# Mergen_Telemetri_Ate_leme.net
KiCad netlist of a schematic drawn in EAGLE
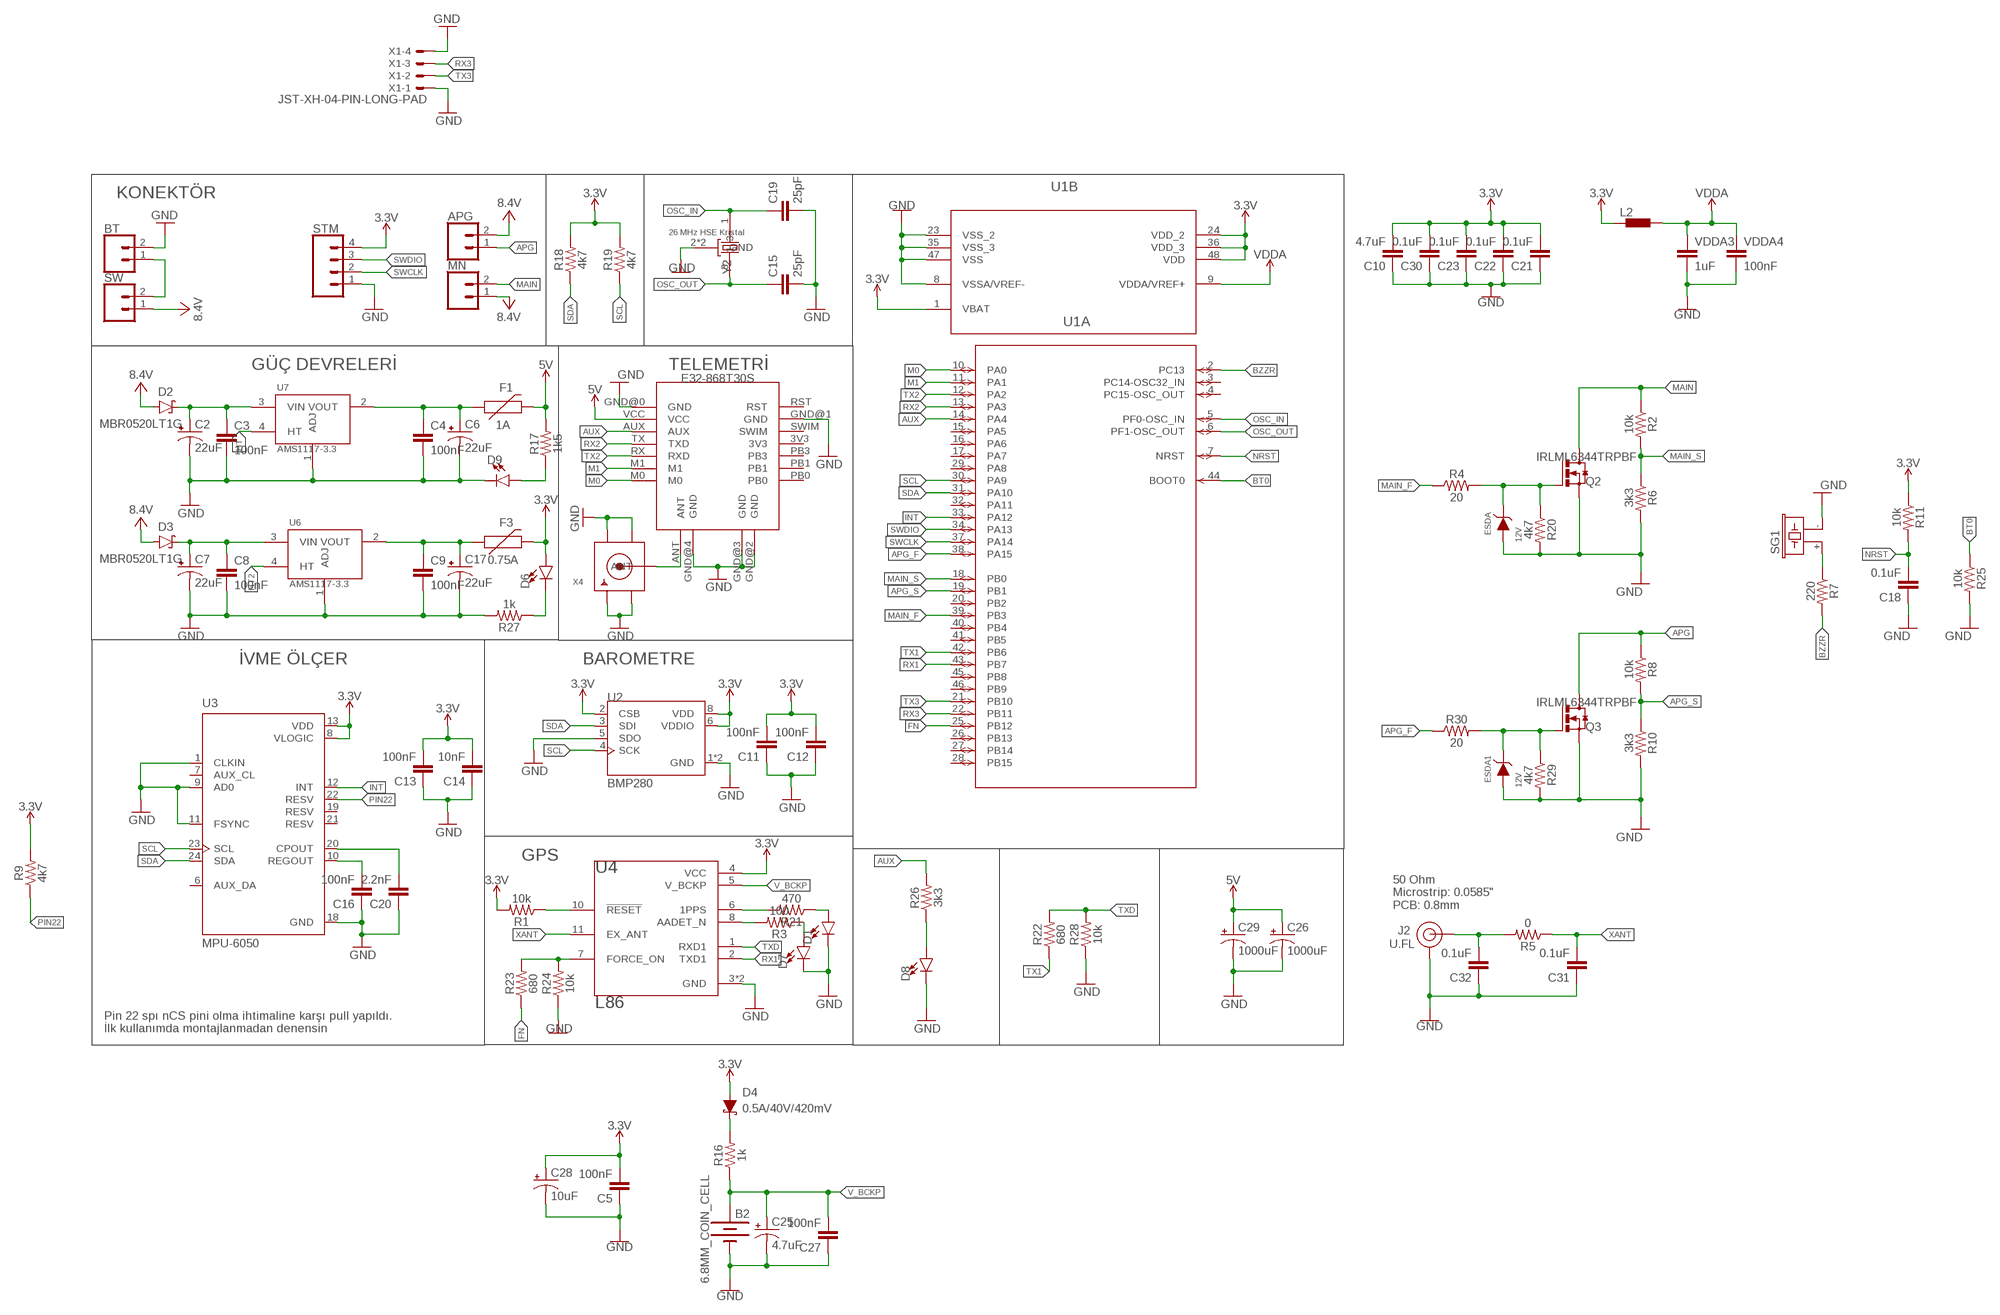
[diagram p0: schematic, sheet 1]

(export (version "E")
  (design (tool "Eeschema 10.0.6"))
  (components
    (comp (ref "APG")
      (value "CONN_02POLAR")
      (footprint "eagle-import:MOLEX-1X2")
      (libsource (lib "eagle-import") (part "CONN_02POLAR"))
    )
    (comp (ref "B2")
      (value "6.8MM_COIN_CELL")
      (footprint "eagle-import:BATTCON-6.8MM")
      (libsource (lib "eagle-import") (part "BATTERY-6.8MM_SMD"))
    )
    (comp (ref "BT")
      (value "CONN_02POLAR")
      (footprint "eagle-import:MOLEX-1X2")
      (libsource (lib "eagle-import") (part "CONN_02POLAR"))
    )
    (comp (ref "C2")
      (value "22uF")
      (footprint "eagle-import:EIA3528")
      (libsource (lib "eagle-import") (part "47UF-POLAR-EIA3528-10V-10%"))
    )
    (comp (ref "C3")
      (value "100nF")
      (footprint "eagle-import:0603")
      (libsource (lib "eagle-import") (part "1.0UF-0603-16V-10%"))
    )
    (comp (ref "C4")
      (value "100nF")
      (footprint "eagle-import:0603")
      (libsource (lib "eagle-import") (part "1.0UF-0603-16V-10%"))
    )
    (comp (ref "C5")
      (value "100nF")
      (footprint "eagle-import:0603")
      (libsource (lib "eagle-import") (part "1.0UF-0603-16V-10%"))
    )
    (comp (ref "C6")
      (value "22uF")
      (footprint "eagle-import:EIA3528")
      (libsource (lib "eagle-import") (part "47UF-POLAR-EIA3528-10V-10%"))
    )
    (comp (ref "C7")
      (value "22uF")
      (footprint "eagle-import:EIA3528")
      (libsource (lib "eagle-import") (part "47UF-POLAR-EIA3528-10V-10%"))
    )
    (comp (ref "C8")
      (value "100nF")
      (footprint "eagle-import:0603")
      (libsource (lib "eagle-import") (part "1.0UF-0603-16V-10%"))
    )
    (comp (ref "C9")
      (value "100nF")
      (footprint "eagle-import:0603")
      (libsource (lib "eagle-import") (part "1.0UF-0603-16V-10%"))
    )
    (comp (ref "C10")
      (value "4.7uF")
      (footprint "eagle-import:0603")
      (libsource (lib "eagle-import") (part "1.0UF-0603-16V-10%"))
    )
    (comp (ref "C11")
      (value "100nF")
      (footprint "eagle-import:0603")
      (libsource (lib "eagle-import") (part "1.0UF-0603-16V-10%"))
    )
    (comp (ref "C12")
      (value "100nF")
      (footprint "eagle-import:0603")
      (libsource (lib "eagle-import") (part "1.0UF-0603-16V-10%"))
    )
    (comp (ref "C13")
      (value "100nF")
      (footprint "eagle-import:0603")
      (libsource (lib "eagle-import") (part "1.0UF-0603-16V-10%"))
    )
    (comp (ref "C14")
      (value "10nF")
      (footprint "eagle-import:0603")
      (libsource (lib "eagle-import") (part "1.0UF-0603-16V-10%"))
    )
    (comp (ref "C15")
      (value "25pF")
      (footprint "eagle-import:0603")
      (libsource (lib "eagle-import") (part "1.0UF-0603-16V-10%"))
    )
    (comp (ref "C16")
      (value "100nF")
      (footprint "eagle-import:0603")
      (libsource (lib "eagle-import") (part "1.0UF-0603-16V-10%"))
    )
    (comp (ref "C17")
      (value "22uF")
      (footprint "eagle-import:EIA3528")
      (libsource (lib "eagle-import") (part "47UF-POLAR-EIA3528-10V-10%"))
    )
    (comp (ref "C18")
      (value "0.1uF")
      (footprint "eagle-import:0603")
      (libsource (lib "eagle-import") (part "1.0UF-0603-16V-10%"))
    )
    (comp (ref "C19")
      (value "25pF")
      (footprint "eagle-import:0603")
      (libsource (lib "eagle-import") (part "1.0UF-0603-16V-10%"))
    )
    (comp (ref "C20")
      (value "2.2nF")
      (footprint "eagle-import:0603")
      (libsource (lib "eagle-import") (part "1.0UF-0603-16V-10%"))
    )
    (comp (ref "C21")
      (value "0.1uF")
      (footprint "eagle-import:0603")
      (libsource (lib "eagle-import") (part "1.0UF-0603-16V-10%"))
    )
    (comp (ref "C22")
      (value "0.1uF")
      (footprint "eagle-import:0603")
      (libsource (lib "eagle-import") (part "1.0UF-0603-16V-10%"))
    )
    (comp (ref "C23")
      (value "0.1uF")
      (footprint "eagle-import:0603")
      (libsource (lib "eagle-import") (part "1.0UF-0603-16V-10%"))
    )
    (comp (ref "C25")
      (value "4.7uF")
      (footprint "eagle-import:EIA3528")
      (libsource (lib "eagle-import") (part "47UF-POLAR-EIA3528-10V-10%"))
    )
    (comp (ref "C26")
      (value "1000uF")
      (footprint "eagle-import:150CLZ-1010")
      (libsource (lib "eagle-import") (part "CPOL-US150CLZ-1010"))
    )
    (comp (ref "C27")
      (value "100nF")
      (footprint "eagle-import:0603")
      (libsource (lib "eagle-import") (part "1.0UF-0603-16V-10%"))
    )
    (comp (ref "C28")
      (value "10uF")
      (footprint "eagle-import:EIA3528")
      (libsource (lib "eagle-import") (part "47UF-POLAR-EIA3528-10V-10%"))
    )
    (comp (ref "C29")
      (value "1000uF")
      (footprint "eagle-import:150CLZ-1010")
      (libsource (lib "eagle-import") (part "CPOL-US150CLZ-1010"))
    )
    (comp (ref "C30")
      (value "0.1uF")
      (footprint "eagle-import:0603")
      (libsource (lib "eagle-import") (part "1.0UF-0603-16V-10%"))
    )
    (comp (ref "C31")
      (value "0.1uF")
      (footprint "eagle-import:0603")
      (libsource (lib "eagle-import") (part "1.0UF-0603-16V-10%"))
    )
    (comp (ref "C32")
      (value "0.1uF")
      (footprint "eagle-import:0603")
      (libsource (lib "eagle-import") (part "1.0UF-0603-16V-10%"))
    )
    (comp (ref "D1")
      (value "LED0603")
      (footprint "eagle-import:LED-0603")
      (libsource (lib "eagle-import") (part "LED0603"))
    )
    (comp (ref "D2")
      (value "MBR0520LT1G")
      (footprint "eagle-import:SODFL3718X115")
      (fields (field (name "MANUFACTURER") "ON Semiconductor"))
      (libsource (lib "eagle-import") (part "SCHOTTKY_DO-219MBR0520LT1G"))
    )
    (comp (ref "D3")
      (value "MBR0520LT1G")
      (footprint "eagle-import:SODFL3718X115")
      (fields (field (name "MANUFACTURER") "ON Semiconductor"))
      (libsource (lib "eagle-import") (part "SCHOTTKY_DO-219MBR0520LT1G"))
    )
    (comp (ref "D4")
      (value "0.5A/40V/420mV")
      (footprint "eagle-import:SOD-323")
      (libsource (lib "eagle-import") (part "DIODE-SCHOTTKY-PMEG4005EJ"))
    )
    (comp (ref "D6")
      (value "LED0603")
      (footprint "eagle-import:LED-0603")
      (libsource (lib "eagle-import") (part "LED0603"))
    )
    (comp (ref "D7")
      (value "LED0603")
      (footprint "eagle-import:LED-0603")
      (libsource (lib "eagle-import") (part "LED0603"))
    )
    (comp (ref "D8")
      (value "LED0603")
      (footprint "eagle-import:LED-0603")
      (libsource (lib "eagle-import") (part "LED0603"))
    )
    (comp (ref "D9")
      (value "LED0603")
      (footprint "eagle-import:LED-0603")
      (libsource (lib "eagle-import") (part "LED0603"))
    )
    (comp (ref "ESDA")
      (value "12V")
      (footprint "eagle-import:WE-TVSP_DO-214AC_UNIDIRECTIONAL")
      (libsource (lib "eagle-import") (part "WE-TVSP_DO-214AC_400W_UNI_824500102"))
    )
    (comp (ref "ESDA1")
      (value "12V")
      (footprint "eagle-import:WE-TVSP_DO-214AC_UNIDIRECTIONAL")
      (libsource (lib "eagle-import") (part "WE-TVSP_DO-214AC_400W_UNI_824500102"))
    )
    (comp (ref "F1")
      (value "1A")
      (footprint "eagle-import:1206")
      (libsource (lib "eagle-import") (part "PPTC_HALF-AMP"))
    )
    (comp (ref "F3")
      (value "0.75A")
      (footprint "eagle-import:1206")
      (libsource (lib "eagle-import") (part "PPTC_HALF-AMP"))
    )
    (comp (ref "J2")
      (value "U.FL")
      (footprint "eagle-import:U.FL")
      (libsource (lib "eagle-import") (part "U.FL2PIN"))
    )
    (comp (ref "L2")
      (value "BLM15HB221SN1")
      (footprint "eagle-import:0402")
      (libsource (lib "eagle-import") (part "BLM15HB221SN1"))
    )
    (comp (ref "MN")
      (value "CONN_02POLAR")
      (footprint "eagle-import:MOLEX-1X2")
      (libsource (lib "eagle-import") (part "CONN_02POLAR"))
    )
    (comp (ref "Q2")
      (value "IRLML6344TRPBF")
      (footprint "eagle-import:SOT23")
      (fields (field (name "MF") "Infineon"))
      (libsource (lib "eagle-import") (part "IRLML6344TRPBF"))
    )
    (comp (ref "Q3")
      (value "IRLML6344TRPBF")
      (footprint "eagle-import:SOT23")
      (fields (field (name "MF") "Infineon"))
      (libsource (lib "eagle-import") (part "IRLML6344TRPBF"))
    )
    (comp (ref "R1")
      (value "10k")
      (footprint "eagle-import:0603")
      (libsource (lib "eagle-import") (part "SparkFun-Resistors_532_1KOHM-0603-1/10W-1%"))
    )
    (comp (ref "R2")
      (value "10k")
      (footprint "eagle-import:0603")
      (libsource (lib "eagle-import") (part "SparkFun-Resistors_532_1KOHM-0603-1/10W-1%"))
    )
    (comp (ref "R3")
      (value "100")
      (footprint "eagle-import:0603")
      (libsource (lib "eagle-import") (part "SparkFun-Resistors_532_1KOHM-0603-1/10W-1%"))
    )
    (comp (ref "R4")
      (value "20")
      (footprint "eagle-import:0603")
      (libsource (lib "eagle-import") (part "SparkFun-Resistors_532_1KOHM-0603-1/10W-1%"))
    )
    (comp (ref "R5")
      (value "0")
      (footprint "eagle-import:0603")
      (libsource (lib "eagle-import") (part "SparkFun-Resistors_532_1KOHM-0603-1/10W-1%"))
    )
    (comp (ref "R6")
      (value "3k3")
      (footprint "eagle-import:0603")
      (libsource (lib "eagle-import") (part "SparkFun-Resistors_532_1KOHM-0603-1/10W-1%"))
    )
    (comp (ref "R7")
      (value "220")
      (footprint "eagle-import:0603")
      (libsource (lib "eagle-import") (part "SparkFun-Resistors_532_1KOHM-0603-1/10W-1%"))
    )
    (comp (ref "R8")
      (value "10k")
      (footprint "eagle-import:0603")
      (libsource (lib "eagle-import") (part "SparkFun-Resistors_532_1KOHM-0603-1/10W-1%"))
    )
    (comp (ref "R9")
      (value "4k7")
      (footprint "eagle-import:0603")
      (libsource (lib "eagle-import") (part "SparkFun-Resistors_532_1KOHM-0603-1/10W-1%"))
    )
    (comp (ref "R10")
      (value "3k3")
      (footprint "eagle-import:0603")
      (libsource (lib "eagle-import") (part "SparkFun-Resistors_532_1KOHM-0603-1/10W-1%"))
    )
    (comp (ref "R11")
      (value "10k")
      (footprint "eagle-import:0603")
      (libsource (lib "eagle-import") (part "SparkFun-Resistors_532_1KOHM-0603-1/10W-1%"))
    )
    (comp (ref "R16")
      (value "1k")
      (footprint "eagle-import:0603")
      (libsource (lib "eagle-import") (part "1KOHM-0603-1/10W-1%"))
    )
    (comp (ref "R17")
      (value "1k5")
      (footprint "eagle-import:0603")
      (libsource (lib "eagle-import") (part "SparkFun-Resistors_532_1KOHM-0603-1/10W-1%"))
    )
    (comp (ref "R18")
      (value "4k7")
      (footprint "eagle-import:0603")
      (libsource (lib "eagle-import") (part "SparkFun-Resistors_532_1KOHM-0603-1/10W-1%"))
    )
    (comp (ref "R19")
      (value "4k7")
      (footprint "eagle-import:0603")
      (libsource (lib "eagle-import") (part "SparkFun-Resistors_532_1KOHM-0603-1/10W-1%"))
    )
    (comp (ref "R20")
      (value "4k7")
      (footprint "eagle-import:0603")
      (libsource (lib "eagle-import") (part "SparkFun-Resistors_532_1KOHM-0603-1/10W-1%"))
    )
    (comp (ref "R21")
      (value "470")
      (footprint "eagle-import:0603")
      (libsource (lib "eagle-import") (part "SparkFun-Resistors_532_1KOHM-0603-1/10W-1%"))
    )
    (comp (ref "R22")
      (value "680")
      (footprint "eagle-import:0603")
      (libsource (lib "eagle-import") (part "SparkFun-Resistors_532_1KOHM-0603-1/10W-1%"))
    )
    (comp (ref "R23")
      (value "680")
      (footprint "eagle-import:0603")
      (libsource (lib "eagle-import") (part "SparkFun-Resistors_532_1KOHM-0603-1/10W-1%"))
    )
    (comp (ref "R24")
      (value "10k")
      (footprint "eagle-import:0603")
      (libsource (lib "eagle-import") (part "SparkFun-Resistors_532_1KOHM-0603-1/10W-1%"))
    )
    (comp (ref "R25")
      (value "10k")
      (footprint "eagle-import:0603")
      (libsource (lib "eagle-import") (part "SparkFun-Resistors_532_1KOHM-0603-1/10W-1%"))
    )
    (comp (ref "R26")
      (value "3k3")
      (footprint "eagle-import:0603")
      (libsource (lib "eagle-import") (part "SparkFun-Resistors_532_1KOHM-0603-1/10W-1%"))
    )
    (comp (ref "R27")
      (value "1k")
      (footprint "eagle-import:0603")
      (libsource (lib "eagle-import") (part "SparkFun-Resistors_532_1KOHM-0603-1/10W-1%"))
    )
    (comp (ref "R28")
      (value "10k")
      (footprint "eagle-import:0603")
      (libsource (lib "eagle-import") (part "SparkFun-Resistors_532_1KOHM-0603-1/10W-1%"))
    )
    (comp (ref "R29")
      (value "4k7")
      (footprint "eagle-import:0603")
      (libsource (lib "eagle-import") (part "SparkFun-Resistors_532_1KOHM-0603-1/10W-1%"))
    )
    (comp (ref "R30")
      (value "20")
      (footprint "eagle-import:0603")
      (libsource (lib "eagle-import") (part "SparkFun-Resistors_532_1KOHM-0603-1/10W-1%"))
    )
    (comp (ref "SG1")
      (value "F/CM12P")
      (footprint "eagle-import:F_CM12P")
      (libsource (lib "eagle-import") (part "F/CM12P"))
    )
    (comp (ref "STM")
      (value "CONN_04")
      (footprint "eagle-import:1X04")
      (libsource (lib "eagle-import") (part "CONN_04"))
    )
    (comp (ref "SW")
      (value "CONN_02POLAR")
      (footprint "eagle-import:MOLEX-1X2")
      (libsource (lib "eagle-import") (part "CONN_02POLAR"))
    )
    (comp (ref "U1")
      (value "STM32F303CCT6")
      (footprint "eagle-import:LQFP48-7X7MM")
      (fields (field (name "COPYRIGHT") "Copyright (C) 2018 Accelerated Designs. All rights reserved"))
      (libsource (lib "eagle-import") (part "STM32F303CCT6"))
    )
    (comp (ref "U2")
      (value "BMP280")
      (footprint "eagle-import:XDCR_BMP280")
      (fields (field (name "MF") "Bosch"))
      (libsource (lib "eagle-import") (part "BMP280"))
    )
    (comp (ref "U3")
      (value "MPU-6050")
      (footprint "eagle-import:QFN50P400X400X95-24N")
      (fields (field (name "MF") "TDK InvenSense"))
      (libsource (lib "eagle-import") (part "MPU-6050"))
    )
    (comp (ref "U4")
      (value "L86")
      (footprint "eagle-import:XCVR_L86")
      (fields (field (name "MF") "Quectel"))
      (libsource (lib "eagle-import") (part "L86"))
    )
    (comp (ref "U5")
      (value "E32-868T30S")
      (footprint "eagle-import:E32-868T30S")
      (libsource (lib "eagle-import") (part "E32-868T30S"))
    )
    (comp (ref "U6")
      (value "AMS1117-3.3")
      (footprint "eagle-import:SOT229P700X180-4N")
      (fields (field (name "MF") "Advanced Monolithic Systems"))
      (libsource (lib "eagle-import") (part "AMS1117-3.3"))
    )
    (comp (ref "U7")
      (value "AMS1117-3.3")
      (footprint "eagle-import:SOT229P700X180-4N")
      (fields (field (name "MF") "Advanced Monolithic Systems"))
      (libsource (lib "eagle-import") (part "AMS1117-3.3"))
    )
    (comp (ref "VDDA3")
      (value "1uF")
      (footprint "eagle-import:0603")
      (libsource (lib "eagle-import") (part "0.1UF-0603-25V-(+80/-20%)"))
    )
    (comp (ref "VDDA4")
      (value "100nF")
      (footprint "eagle-import:0603")
      (libsource (lib "eagle-import") (part "0.1UF-0603-25V-(+80/-20%)"))
    )
    (comp (ref "X1")
      (value "JST-XH-04-PIN-LONG-PAD")
      (footprint "eagle-import:JST-XH-04-PACKAGE-LONG-PAD")
      (libsource (lib "eagle-import") (part "JST-XH-04-PIN-LONG-PAD"))
    )
    (comp (ref "X4")
      (value "SMACONNECTOR")
      (footprint "eagle-import:SMA90_DIP")
      (libsource (lib "eagle-import") (part "SMACONNECTOR"))
    )
    (comp (ref "Y2")
      (value "ABM3B-26.000MHZ-10-1-U-T")
      (footprint "eagle-import:OSCCC500X320X110-4N")
      (fields (field (name "MF") "Abracon"))
      (libsource (lib "eagle-import") (part "ABM3B-26.000MHZ-10-1-U-T"))
    )
  )
  (nets
    (net (code "1") (name "3.3V") (class "Default")
      (node (ref "C10") (pin "2") (pinfunction "2_2") (pintype "passive"))
      (node (ref "C11") (pin "2") (pinfunction "2_2") (pintype "passive"))
      (node (ref "C12") (pin "2") (pinfunction "2_2") (pintype "passive"))
      (node (ref "C13") (pin "2") (pinfunction "2_2") (pintype "passive"))
      (node (ref "C14") (pin "2") (pinfunction "2_2") (pintype "passive"))
      (node (ref "C21") (pin "2") (pinfunction "2_2") (pintype "passive"))
      (node (ref "C22") (pin "2") (pinfunction "2_2") (pintype "passive"))
      (node (ref "C23") (pin "2") (pinfunction "2_2") (pintype "passive"))
      (node (ref "C28") (pin "A") (pinfunction "+_A") (pintype "passive"))
      (node (ref "C30") (pin "2") (pinfunction "2_2") (pintype "passive"))
      (node (ref "C5") (pin "2") (pinfunction "2_2") (pintype "passive"))
      (node (ref "D4") (pin "A") (pinfunction "A_A") (pintype "passive"))
      (node (ref "D6") (pin "A") (pinfunction "A_A") (pintype "passive"))
      (node (ref "F3") (pin "2") (pinfunction "2_2") (pintype "bidirectional"))
      (node (ref "L2") (pin "1") (pinfunction "1_1") (pintype "passive"))
      (node (ref "R1") (pin "2") (pinfunction "2_2") (pintype "passive"))
      (node (ref "R11") (pin "1") (pinfunction "1_1") (pintype "passive"))
      (node (ref "R18") (pin "2") (pinfunction "2_2") (pintype "passive"))
      (node (ref "R19") (pin "2") (pinfunction "2_2") (pintype "passive"))
      (node (ref "R9") (pin "2") (pinfunction "2_2") (pintype "passive"))
      (node (ref "STM") (pin "4") (pinfunction "4_4") (pintype "passive"))
      (node (ref "U1") (pin "1") (pinfunction "VBAT_1") (pintype "power_in"))
      (node (ref "U1") (pin "24") (pinfunction "VDD_2_24") (pintype "power_in"))
      (node (ref "U1") (pin "36") (pinfunction "VDD_3_36") (pintype "power_in"))
      (node (ref "U1") (pin "48") (pinfunction "VDD_48") (pintype "power_in"))
      (node (ref "U2") (pin "2") (pinfunction "CSB_2") (pintype "input"))
      (node (ref "U2") (pin "6") (pinfunction "VDDIO_6") (pintype "power_in"))
      (node (ref "U2") (pin "8") (pinfunction "VDD_8") (pintype "power_in"))
      (node (ref "U3") (pin "13") (pinfunction "VDD_13") (pintype "power_in"))
      (node (ref "U3") (pin "8") (pinfunction "VLOGIC_8") (pintype "power_in"))
      (node (ref "U4") (pin "4") (pinfunction "VCC_4") (pintype "power_in"))
    )
    (net (code "2") (name "5V") (class "Default")
      (node (ref "C26") (pin "+") (pinfunction "+_+") (pintype "passive"))
      (node (ref "C29") (pin "+") (pinfunction "+_+") (pintype "passive"))
      (node (ref "F1") (pin "2") (pinfunction "2_2") (pintype "bidirectional"))
      (node (ref "R17") (pin "2") (pinfunction "2_2") (pintype "passive"))
      (node (ref "U5") (pin "VCC") (pinfunction "VCC_VCC") (pintype "bidirectional"))
    )
    (net (code "3") (name "8.4V") (class "Default")
      (node (ref "APG") (pin "2") (pinfunction "2_2") (pintype "passive"))
      (node (ref "D2") (pin "2") (pinfunction "A_2") (pintype "passive"))
      (node (ref "D3") (pin "2") (pinfunction "A_2") (pintype "passive"))
      (node (ref "MN") (pin "1") (pinfunction "1_1") (pintype "passive"))
      (node (ref "SW") (pin "1") (pinfunction "1_1") (pintype "passive"))
    )
    (net (code "4") (name "APG") (class "Default")
      (node (ref "APG") (pin "1") (pinfunction "1_1") (pintype "passive"))
      (node (ref "Q3") (pin "3") (pinfunction "D_3") (pintype "passive"))
      (node (ref "R8") (pin "1") (pinfunction "1_1") (pintype "passive"))
    )
    (net (code "5") (name "APG_F") (class "Default")
      (node (ref "R30") (pin "1") (pinfunction "1_1") (pintype "passive"))
      (node (ref "U1") (pin "38") (pinfunction "PA15_38") (pintype "bidirectional"))
    )
    (net (code "6") (name "APG_S") (class "Default")
      (node (ref "R10") (pin "1") (pinfunction "1_1") (pintype "passive"))
      (node (ref "R8") (pin "2") (pinfunction "2_2") (pintype "passive"))
      (node (ref "U1") (pin "19") (pinfunction "PB1_19") (pintype "bidirectional"))
    )
    (net (code "7") (name "AUX") (class "Default")
      (node (ref "R26") (pin "2") (pinfunction "2_2") (pintype "passive"))
      (node (ref "U1") (pin "14") (pinfunction "PA4_14") (pintype "bidirectional"))
      (node (ref "U5") (pin "AUX") (pinfunction "AUX_AUX") (pintype "bidirectional"))
    )
    (net (code "8") (name "BT0") (class "Default")
      (node (ref "R25") (pin "1") (pinfunction "1_1") (pintype "passive"))
      (node (ref "U1") (pin "44") (pinfunction "BOOT0_44") (pintype "input"))
    )
    (net (code "9") (name "BZZR") (class "Default")
      (node (ref "R7") (pin "2") (pinfunction "2_2") (pintype "passive"))
      (node (ref "U1") (pin "2") (pinfunction "PC13_2") (pintype "bidirectional"))
    )
    (net (code "10") (name "FN") (class "Default")
      (node (ref "R23") (pin "1") (pinfunction "1_1") (pintype "passive"))
      (node (ref "U1") (pin "25") (pinfunction "PB12_25") (pintype "bidirectional"))
    )
    (net (code "11") (name "GND") (class "Default")
      (node (ref "B2") (pin "-") (pinfunction "-_-") (pintype "power_in"))
      (node (ref "BT") (pin "2") (pinfunction "2_2") (pintype "passive"))
      (node (ref "C10") (pin "1") (pinfunction "1_1") (pintype "passive"))
      (node (ref "C11") (pin "1") (pinfunction "1_1") (pintype "passive"))
      (node (ref "C12") (pin "1") (pinfunction "1_1") (pintype "passive"))
      (node (ref "C13") (pin "1") (pinfunction "1_1") (pintype "passive"))
      (node (ref "C14") (pin "1") (pinfunction "1_1") (pintype "passive"))
      (node (ref "C15") (pin "2") (pinfunction "2_2") (pintype "passive"))
      (node (ref "C16") (pin "1") (pinfunction "1_1") (pintype "passive"))
      (node (ref "C17") (pin "C") (pinfunction "-_C") (pintype "passive"))
      (node (ref "C18") (pin "1") (pinfunction "1_1") (pintype "passive"))
      (node (ref "C19") (pin "2") (pinfunction "2_2") (pintype "passive"))
      (node (ref "C2") (pin "C") (pinfunction "-_C") (pintype "passive"))
      (node (ref "C20") (pin "1") (pinfunction "1_1") (pintype "passive"))
      (node (ref "C21") (pin "1") (pinfunction "1_1") (pintype "passive"))
      (node (ref "C22") (pin "1") (pinfunction "1_1") (pintype "passive"))
      (node (ref "C23") (pin "1") (pinfunction "1_1") (pintype "passive"))
      (node (ref "C25") (pin "C") (pinfunction "-_C") (pintype "passive"))
      (node (ref "C26") (pin "-") (pinfunction "-_-") (pintype "passive"))
      (node (ref "C27") (pin "1") (pinfunction "1_1") (pintype "passive"))
      (node (ref "C28") (pin "C") (pinfunction "-_C") (pintype "passive"))
      (node (ref "C29") (pin "-") (pinfunction "-_-") (pintype "passive"))
      (node (ref "C3") (pin "2") (pinfunction "2_2") (pintype "passive"))
      (node (ref "C30") (pin "1") (pinfunction "1_1") (pintype "passive"))
      (node (ref "C31") (pin "1") (pinfunction "1_1") (pintype "passive"))
      (node (ref "C32") (pin "1") (pinfunction "1_1") (pintype "passive"))
      (node (ref "C4") (pin "2") (pinfunction "2_2") (pintype "passive"))
      (node (ref "C5") (pin "1") (pinfunction "1_1") (pintype "passive"))
      (node (ref "C6") (pin "C") (pinfunction "-_C") (pintype "passive"))
      (node (ref "C7") (pin "C") (pinfunction "-_C") (pintype "passive"))
      (node (ref "C8") (pin "2") (pinfunction "2_2") (pintype "passive"))
      (node (ref "C9") (pin "2") (pinfunction "2_2") (pintype "passive"))
      (node (ref "D1") (pin "C") (pinfunction "C_C") (pintype "passive"))
      (node (ref "D7") (pin "C") (pinfunction "C_C") (pintype "passive"))
      (node (ref "D8") (pin "C") (pinfunction "C_C") (pintype "passive"))
      (node (ref "D9") (pin "C") (pinfunction "C_C") (pintype "passive"))
      (node (ref "ESDA") (pin "2") (pinfunction "A_2") (pintype "passive"))
      (node (ref "ESDA1") (pin "2") (pinfunction "A_2") (pintype "passive"))
      (node (ref "J2") (pin "1") (pinfunction "GND_1") (pintype "bidirectional"))
      (node (ref "J2") (pin "2") (pinfunction "GND_2") (pintype "bidirectional"))
      (node (ref "Q2") (pin "2") (pinfunction "S_2") (pintype "passive"))
      (node (ref "Q3") (pin "2") (pinfunction "S_2") (pintype "passive"))
      (node (ref "R10") (pin "2") (pinfunction "2_2") (pintype "passive"))
      (node (ref "R20") (pin "2") (pinfunction "2_2") (pintype "passive"))
      (node (ref "R24") (pin "1") (pinfunction "1_1") (pintype "passive"))
      (node (ref "R25") (pin "2") (pinfunction "2_2") (pintype "passive"))
      (node (ref "R27") (pin "2") (pinfunction "2_2") (pintype "passive"))
      (node (ref "R28") (pin "1") (pinfunction "1_1") (pintype "passive"))
      (node (ref "R29") (pin "2") (pinfunction "2_2") (pintype "passive"))
      (node (ref "R6") (pin "2") (pinfunction "2_2") (pintype "passive"))
      (node (ref "SG1") (pin "-") (pinfunction "2_-") (pintype "passive"))
      (node (ref "STM") (pin "1") (pinfunction "1_1") (pintype "passive"))
      (node (ref "U1") (pin "23") (pinfunction "VSS_2_23") (pintype "power_in"))
      (node (ref "U1") (pin "35") (pinfunction "VSS_3_35") (pintype "power_in"))
      (node (ref "U1") (pin "47") (pinfunction "VSS_47") (pintype "power_in"))
      (node (ref "U1") (pin "8") (pinfunction "VSSA/VREF-_8") (pintype "power_in"))
      (node (ref "U2") (pin "1") (pinfunction "GND_1") (pintype "power_in"))
      (node (ref "U2") (pin "5") (pinfunction "SDO_5") (pintype "bidirectional"))
      (node (ref "U2") (pin "7") (pinfunction "GND_7") (pintype "power_in"))
      (node (ref "U3") (pin "1") (pinfunction "CLKIN_1") (pintype "input"))
      (node (ref "U3") (pin "11") (pinfunction "FSYNC_11") (pintype "input"))
      (node (ref "U3") (pin "18") (pinfunction "GND_18") (pintype "power_in"))
      (node (ref "U3") (pin "9") (pinfunction "AD0_9") (pintype "input"))
      (node (ref "U4") (pin "12") (pinfunction "GND_12") (pintype "passive"))
      (node (ref "U4") (pin "3") (pinfunction "GND_3") (pintype "passive"))
      (node (ref "U5") (pin "GND@0") (pinfunction "GND_GND@0") (pintype "bidirectional"))
      (node (ref "U5") (pin "GND@1") (pinfunction "GND_GND@1") (pintype "bidirectional"))
      (node (ref "U5") (pin "GND@2") (pinfunction "GND_GND@2") (pintype "bidirectional"))
      (node (ref "U5") (pin "GND@3") (pinfunction "GND_GND@3") (pintype "bidirectional"))
      (node (ref "U5") (pin "GND@4") (pinfunction "GND_GND@4") (pintype "bidirectional"))
      (node (ref "U6") (pin "1") (pinfunction "ADJ_1") (pintype "power_in"))
      (node (ref "U7") (pin "1") (pinfunction "ADJ_1") (pintype "power_in"))
      (node (ref "VDDA3") (pin "2") (pinfunction "2_2") (pintype "passive"))
      (node (ref "VDDA4") (pin "2") (pinfunction "2_2") (pintype "passive"))
      (node (ref "X1") (pin "1") (pinfunction "S_1") (pintype "passive"))
      (node (ref "X1") (pin "4") (pinfunction "S_4") (pintype "passive"))
      (node (ref "X4") (pin "GND1") (pinfunction "GND1_GND1") (pintype "power_in"))
      (node (ref "X4") (pin "GND2") (pinfunction "GND2_GND2") (pintype "power_in"))
      (node (ref "X4") (pin "GND3") (pinfunction "GND3_GND3") (pintype "power_in"))
      (node (ref "X4") (pin "GND4") (pinfunction "GND4_GND4") (pintype "power_in"))
      (node (ref "Y2") (pin "2") (pinfunction "GND_2") (pintype "passive"))
      (node (ref "Y2") (pin "4") (pinfunction "GND_4") (pintype "passive"))
    )
    (net (code "12") (name "HT") (class "Default")
      (node (ref "U7") (pin "4") (pinfunction "HT_4") (pintype "bidirectional"))
    )
    (net (code "13") (name "HT2") (class "Default")
      (node (ref "U6") (pin "4") (pinfunction "HT_4") (pintype "bidirectional"))
    )
    (net (code "14") (name "INT") (class "Default")
      (node (ref "U1") (pin "33") (pinfunction "PA12_33") (pintype "bidirectional"))
      (node (ref "U3") (pin "12") (pinfunction "INT_12") (pintype "output"))
    )
    (net (code "15") (name "M0") (class "Default")
      (node (ref "U1") (pin "10") (pinfunction "PA0_10") (pintype "bidirectional"))
      (node (ref "U5") (pin "M0") (pinfunction "M0_M0") (pintype "bidirectional"))
    )
    (net (code "16") (name "M1") (class "Default")
      (node (ref "U1") (pin "11") (pinfunction "PA1_11") (pintype "bidirectional"))
      (node (ref "U5") (pin "M1") (pinfunction "M1_M1") (pintype "bidirectional"))
    )
    (net (code "17") (name "MAIN") (class "Default")
      (node (ref "MN") (pin "2") (pinfunction "2_2") (pintype "passive"))
      (node (ref "Q2") (pin "3") (pinfunction "D_3") (pintype "passive"))
      (node (ref "R2") (pin "1") (pinfunction "1_1") (pintype "passive"))
    )
    (net (code "18") (name "MAIN_F") (class "Default")
      (node (ref "R4") (pin "1") (pinfunction "1_1") (pintype "passive"))
      (node (ref "U1") (pin "39") (pinfunction "PB3_39") (pintype "bidirectional"))
    )
    (net (code "19") (name "MAIN_S") (class "Default")
      (node (ref "R2") (pin "2") (pinfunction "2_2") (pintype "passive"))
      (node (ref "R6") (pin "1") (pinfunction "1_1") (pintype "passive"))
      (node (ref "U1") (pin "18") (pinfunction "PB0_18") (pintype "bidirectional"))
    )
    (net (code "20") (name "NRST") (class "Default")
      (node (ref "C18") (pin "2") (pinfunction "2_2") (pintype "passive"))
      (node (ref "R11") (pin "2") (pinfunction "2_2") (pintype "passive"))
      (node (ref "U1") (pin "7") (pinfunction "NRST_7") (pintype "bidirectional"))
    )
    (net (code "21") (name "Net-(BT-Pad1)") (class "Default")
      (node (ref "BT") (pin "1") (pinfunction "1_1") (pintype "passive"))
      (node (ref "SW") (pin "2") (pinfunction "2_2") (pintype "passive"))
    )
    (net (code "22") (name "Net-(C2-+)") (class "Default")
      (node (ref "C2") (pin "A") (pinfunction "+_A") (pintype "passive"))
      (node (ref "C3") (pin "1") (pinfunction "1_1") (pintype "passive"))
      (node (ref "D2") (pin "1") (pinfunction "C_1") (pintype "passive"))
      (node (ref "U7") (pin "3") (pinfunction "VIN_3") (pintype "input"))
    )
    (net (code "23") (name "Net-(C6-+)") (class "Default")
      (node (ref "C4") (pin "1") (pinfunction "1_1") (pintype "passive"))
      (node (ref "C6") (pin "A") (pinfunction "+_A") (pintype "passive"))
      (node (ref "F1") (pin "1") (pinfunction "1_1") (pintype "bidirectional"))
      (node (ref "U7") (pin "2") (pinfunction "VOUT_2") (pintype "output"))
    )
    (net (code "24") (name "Net-(C7-+)") (class "Default")
      (node (ref "C7") (pin "A") (pinfunction "+_A") (pintype "passive"))
      (node (ref "C8") (pin "1") (pinfunction "1_1") (pintype "passive"))
      (node (ref "D3") (pin "1") (pinfunction "C_1") (pintype "passive"))
      (node (ref "U6") (pin "3") (pinfunction "VIN_3") (pintype "input"))
    )
    (net (code "25") (name "Net-(C17-+)") (class "Default")
      (node (ref "C17") (pin "A") (pinfunction "+_A") (pintype "passive"))
      (node (ref "C9") (pin "1") (pinfunction "1_1") (pintype "passive"))
      (node (ref "F3") (pin "1") (pinfunction "1_1") (pintype "bidirectional"))
      (node (ref "U6") (pin "2") (pinfunction "VOUT_2") (pintype "output"))
    )
    (net (code "26") (name "Net-(D1-PadA)") (class "Default")
      (node (ref "D1") (pin "A") (pinfunction "A_A") (pintype "passive"))
      (node (ref "R21") (pin "1") (pinfunction "1_1") (pintype "passive"))
    )
    (net (code "27") (name "Net-(D4-PadC)") (class "Default")
      (node (ref "D4") (pin "C") (pinfunction "C_C") (pintype "passive"))
      (node (ref "R16") (pin "2") (pinfunction "2_2") (pintype "passive"))
    )
    (net (code "28") (name "Net-(D6-PadC)") (class "Default")
      (node (ref "D6") (pin "C") (pinfunction "C_C") (pintype "passive"))
      (node (ref "R27") (pin "1") (pinfunction "1_1") (pintype "passive"))
    )
    (net (code "29") (name "Net-(D7-PadA)") (class "Default")
      (node (ref "D7") (pin "A") (pinfunction "A_A") (pintype "passive"))
      (node (ref "R3") (pin "1") (pinfunction "1_1") (pintype "passive"))
    )
    (net (code "30") (name "Net-(D8-PadA)") (class "Default")
      (node (ref "D8") (pin "A") (pinfunction "A_A") (pintype "passive"))
      (node (ref "R26") (pin "1") (pinfunction "1_1") (pintype "passive"))
    )
    (net (code "31") (name "Net-(D9-PadA)") (class "Default")
      (node (ref "D9") (pin "A") (pinfunction "A_A") (pintype "passive"))
      (node (ref "R17") (pin "1") (pinfunction "1_1") (pintype "passive"))
    )
    (net (code "32") (name "Net-(ESDA-C)") (class "Default")
      (node (ref "ESDA") (pin "1") (pinfunction "C_1") (pintype "passive"))
      (node (ref "Q2") (pin "1") (pinfunction "G_1") (pintype "passive"))
      (node (ref "R20") (pin "1") (pinfunction "1_1") (pintype "passive"))
      (node (ref "R4") (pin "2") (pinfunction "2_2") (pintype "passive"))
    )
    (net (code "33") (name "Net-(ESDA1-C)") (class "Default")
      (node (ref "ESDA1") (pin "1") (pinfunction "C_1") (pintype "passive"))
      (node (ref "Q3") (pin "1") (pinfunction "G_1") (pintype "passive"))
      (node (ref "R29") (pin "1") (pinfunction "1_1") (pintype "passive"))
      (node (ref "R30") (pin "2") (pinfunction "2_2") (pintype "passive"))
    )
    (net (code "34") (name "Net-(J2-SIGNAL)") (class "Default")
      (node (ref "C32") (pin "2") (pinfunction "2_2") (pintype "passive"))
      (node (ref "J2") (pin "FEED") (pinfunction "SIGNAL_FEED") (pintype "bidirectional"))
      (node (ref "R5") (pin "2") (pinfunction "2_2") (pintype "passive"))
    )
    (net (code "35") (name "Net-(SG1-1)") (class "Default")
      (node (ref "R7") (pin "1") (pinfunction "1_1") (pintype "passive"))
      (node (ref "SG1") (pin "+") (pinfunction "1_+") (pintype "passive"))
    )
    (net (code "36") (name "Net-(U3-CPOUT)") (class "Default")
      (node (ref "C20") (pin "2") (pinfunction "2_2") (pintype "passive"))
      (node (ref "U3") (pin "20") (pinfunction "CPOUT_20") (pintype "passive"))
    )
    (net (code "37") (name "Net-(U3-REGOUT)") (class "Default")
      (node (ref "C16") (pin "2") (pinfunction "2_2") (pintype "passive"))
      (node (ref "U3") (pin "10") (pinfunction "REGOUT_10") (pintype "passive"))
    )
    (net (code "38") (name "Net-(U4-1PPS)") (class "Default")
      (node (ref "R21") (pin "2") (pinfunction "2_2") (pintype "passive"))
      (node (ref "U4") (pin "6") (pinfunction "1PPS_6") (pintype "output"))
    )
    (net (code "39") (name "Net-(U4-AADET_N)") (class "Default")
      (node (ref "R3") (pin "2") (pinfunction "2_2") (pintype "passive"))
      (node (ref "U4") (pin "8") (pinfunction "AADET_N_8") (pintype "output"))
    )
    (net (code "40") (name "Net-(U4-FORCE_ON)") (class "Default")
      (node (ref "R23") (pin "2") (pinfunction "2_2") (pintype "passive"))
      (node (ref "R24") (pin "2") (pinfunction "2_2") (pintype "passive"))
      (node (ref "U4") (pin "7") (pinfunction "FORCE_ON_7") (pintype "input"))
    )
    (net (code "41") (name "Net-(U4-~{RESET})") (class "Default")
      (node (ref "R1") (pin "1") (pinfunction "1_1") (pintype "passive"))
      (node (ref "U4") (pin "10") (pinfunction "~{RESET}_10") (pintype "input"))
    )
    (net (code "42") (name "Net-(X4-ANT)") (class "Default")
      (node (ref "U5") (pin "ANT") (pinfunction "ANT_ANT") (pintype "bidirectional"))
      (node (ref "X4") (pin "ANTENNA") (pinfunction "ANT_ANTENNA") (pintype "bidirectional"))
    )
    (net (code "43") (name "OSC_IN") (class "Default")
      (node (ref "C19") (pin "1") (pinfunction "1_1") (pintype "passive"))
      (node (ref "U1") (pin "5") (pinfunction "PF0-OSC_IN_5") (pintype "bidirectional"))
      (node (ref "Y2") (pin "1") (pinfunction "1_1") (pintype "passive"))
    )
    (net (code "44") (name "OSC_OUT") (class "Default")
      (node (ref "C15") (pin "1") (pinfunction "1_1") (pintype "passive"))
      (node (ref "U1") (pin "6") (pinfunction "PF1-OSC_OUT_6") (pintype "bidirectional"))
      (node (ref "Y2") (pin "3") (pinfunction "3_3") (pintype "passive"))
    )
    (net (code "45") (name "PIN22") (class "Default")
      (node (ref "R9") (pin "1") (pinfunction "1_1") (pintype "passive"))
      (node (ref "U3") (pin "22") (pinfunction "RESV_22") (pintype "passive"))
    )
    (net (code "46") (name "RX1") (class "Default")
      (node (ref "U1") (pin "43") (pinfunction "PB7_43") (pintype "bidirectional"))
      (node (ref "U4") (pin "2") (pinfunction "TXD1_2") (pintype "output"))
    )
    (net (code "47") (name "RX2") (class "Default")
      (node (ref "U1") (pin "13") (pinfunction "PA3_13") (pintype "bidirectional"))
      (node (ref "U5") (pin "TX") (pinfunction "TXD_TX") (pintype "bidirectional"))
    )
    (net (code "48") (name "RX3") (class "Default")
      (node (ref "U1") (pin "22") (pinfunction "PB11_22") (pintype "bidirectional"))
      (node (ref "X1") (pin "3") (pinfunction "S_3") (pintype "passive"))
    )
    (net (code "49") (name "SCL") (class "Default")
      (node (ref "R19") (pin "1") (pinfunction "1_1") (pintype "passive"))
      (node (ref "U1") (pin "30") (pinfunction "PA9_30") (pintype "bidirectional"))
      (node (ref "U2") (pin "4") (pinfunction "SCK_4") (pintype "input"))
      (node (ref "U3") (pin "23") (pinfunction "SCL_23") (pintype "input"))
    )
    (net (code "50") (name "SDA") (class "Default")
      (node (ref "R18") (pin "1") (pinfunction "1_1") (pintype "passive"))
      (node (ref "U1") (pin "31") (pinfunction "PA10_31") (pintype "bidirectional"))
      (node (ref "U2") (pin "3") (pinfunction "SDI_3") (pintype "bidirectional"))
      (node (ref "U3") (pin "24") (pinfunction "SDA_24") (pintype "bidirectional"))
    )
    (net (code "51") (name "SWCLK") (class "Default")
      (node (ref "STM") (pin "2") (pinfunction "2_2") (pintype "passive"))
      (node (ref "U1") (pin "37") (pinfunction "PA14_37") (pintype "bidirectional"))
    )
    (net (code "52") (name "SWDIO") (class "Default")
      (node (ref "STM") (pin "3") (pinfunction "3_3") (pintype "passive"))
      (node (ref "U1") (pin "34") (pinfunction "PA13_34") (pintype "bidirectional"))
    )
    (net (code "53") (name "TX1") (class "Default")
      (node (ref "R22") (pin "1") (pinfunction "1_1") (pintype "passive"))
      (node (ref "U1") (pin "42") (pinfunction "PB6_42") (pintype "bidirectional"))
    )
    (net (code "54") (name "TX2") (class "Default")
      (node (ref "U1") (pin "12") (pinfunction "PA2_12") (pintype "bidirectional"))
      (node (ref "U5") (pin "RX") (pinfunction "RXD_RX") (pintype "bidirectional"))
    )
    (net (code "55") (name "TX3") (class "Default")
      (node (ref "U1") (pin "21") (pinfunction "PB10_21") (pintype "bidirectional"))
      (node (ref "X1") (pin "2") (pinfunction "S_2") (pintype "passive"))
    )
    (net (code "56") (name "TXD") (class "Default")
      (node (ref "R22") (pin "2") (pinfunction "2_2") (pintype "passive"))
      (node (ref "R28") (pin "2") (pinfunction "2_2") (pintype "passive"))
      (node (ref "U4") (pin "1") (pinfunction "RXD1_1") (pintype "input"))
    )
    (net (code "57") (name "VDDA") (class "Default")
      (node (ref "L2") (pin "2") (pinfunction "2_2") (pintype "passive"))
      (node (ref "U1") (pin "9") (pinfunction "VDDA/VREF+_9") (pintype "power_in"))
      (node (ref "VDDA3") (pin "1") (pinfunction "1_1") (pintype "passive"))
      (node (ref "VDDA4") (pin "1") (pinfunction "1_1") (pintype "passive"))
    )
    (net (code "58") (name "V_BCKP") (class "Default")
      (node (ref "B2") (pin "+") (pinfunction "+_+") (pintype "power_in"))
      (node (ref "C25") (pin "A") (pinfunction "+_A") (pintype "passive"))
      (node (ref "C27") (pin "2") (pinfunction "2_2") (pintype "passive"))
      (node (ref "R16") (pin "1") (pinfunction "1_1") (pintype "passive"))
      (node (ref "U4") (pin "5") (pinfunction "V_BCKP_5") (pintype "power_in"))
    )
    (net (code "59") (name "XANT") (class "Default")
      (node (ref "C31") (pin "2") (pinfunction "2_2") (pintype "passive"))
      (node (ref "R5") (pin "1") (pinfunction "1_1") (pintype "passive"))
      (node (ref "U4") (pin "11") (pinfunction "EX_ANT_11") (pintype "input"))
    )
    (net (code "60") (name "unconnected-(U1A-PA5-Pad15)") (class "Default")
      (node (ref "U1") (pin "15") (pinfunction "PA5_15") (pintype "bidirectional"))
    )
    (net (code "61") (name "unconnected-(U1A-PA6-Pad16)") (class "Default")
      (node (ref "U1") (pin "16") (pinfunction "PA6_16") (pintype "bidirectional"))
    )
    (net (code "62") (name "unconnected-(U1A-PA7-Pad17)") (class "Default")
      (node (ref "U1") (pin "17") (pinfunction "PA7_17") (pintype "bidirectional"))
    )
    (net (code "63") (name "unconnected-(U1A-PA8-Pad29)") (class "Default")
      (node (ref "U1") (pin "29") (pinfunction "PA8_29") (pintype "bidirectional"))
    )
    (net (code "64") (name "unconnected-(U1A-PA11-Pad32)") (class "Default")
      (node (ref "U1") (pin "32") (pinfunction "PA11_32") (pintype "bidirectional"))
    )
    (net (code "65") (name "unconnected-(U1A-PB2-Pad20)") (class "Default")
      (node (ref "U1") (pin "20") (pinfunction "PB2_20") (pintype "bidirectional"))
    )
    (net (code "66") (name "unconnected-(U1A-PB4-Pad40)") (class "Default")
      (node (ref "U1") (pin "40") (pinfunction "PB4_40") (pintype "bidirectional"))
    )
    (net (code "67") (name "unconnected-(U1A-PB5-Pad41)") (class "Default")
      (node (ref "U1") (pin "41") (pinfunction "PB5_41") (pintype "bidirectional"))
    )
    (net (code "68") (name "unconnected-(U1A-PB8-Pad45)") (class "Default")
      (node (ref "U1") (pin "45") (pinfunction "PB8_45") (pintype "bidirectional"))
    )
    (net (code "69") (name "unconnected-(U1A-PB9-Pad46)") (class "Default")
      (node (ref "U1") (pin "46") (pinfunction "PB9_46") (pintype "bidirectional"))
    )
    (net (code "70") (name "unconnected-(U1A-PB13-Pad26)") (class "Default")
      (node (ref "U1") (pin "26") (pinfunction "PB13_26") (pintype "bidirectional"))
    )
    (net (code "71") (name "unconnected-(U1A-PB14-Pad27)") (class "Default")
      (node (ref "U1") (pin "27") (pinfunction "PB14_27") (pintype "bidirectional"))
    )
    (net (code "72") (name "unconnected-(U1A-PB15-Pad28)") (class "Default")
      (node (ref "U1") (pin "28") (pinfunction "PB15_28") (pintype "bidirectional"))
    )
    (net (code "73") (name "unconnected-(U1A-PC14-OSC32_IN-Pad3)") (class "Default")
      (node (ref "U1") (pin "3") (pinfunction "PC14-OSC32_IN_3") (pintype "bidirectional"))
    )
    (net (code "74") (name "unconnected-(U1A-PC15-OSC_OUT-Pad4)") (class "Default")
      (node (ref "U1") (pin "4") (pinfunction "PC15-OSC_OUT_4") (pintype "bidirectional"))
    )
    (net (code "75") (name "unconnected-(U3-AUX_CL-Pad7)") (class "Default")
      (node (ref "U3") (pin "7") (pinfunction "AUX_CL_7") (pintype "input"))
    )
    (net (code "76") (name "unconnected-(U3-AUX_DA-Pad6)") (class "Default")
      (node (ref "U3") (pin "6") (pinfunction "AUX_DA_6") (pintype "bidirectional"))
    )
    (net (code "77") (name "unconnected-(U3-RESV-Pad19)") (class "Default")
      (node (ref "U3") (pin "19") (pinfunction "RESV_19") (pintype "passive"))
    )
    (net (code "78") (name "unconnected-(U3-RESV-Pad21)") (class "Default")
      (node (ref "U3") (pin "21") (pinfunction "RESV_21") (pintype "passive"))
    )
    (net (code "79") (name "unconnected-(U5-Pad3V3)") (class "Default")
      (node (ref "U5") (pin "3V3") (pinfunction "3V3_3V3") (pintype "bidirectional"))
    )
    (net (code "80") (name "unconnected-(U5-PadPB0)") (class "Default")
      (node (ref "U5") (pin "PB0") (pinfunction "PB0_PB0") (pintype "bidirectional"))
    )
    (net (code "81") (name "unconnected-(U5-PadPB1)") (class "Default")
      (node (ref "U5") (pin "PB1") (pinfunction "PB1_PB1") (pintype "bidirectional"))
    )
    (net (code "82") (name "unconnected-(U5-PadPB3)") (class "Default")
      (node (ref "U5") (pin "PB3") (pinfunction "PB3_PB3") (pintype "bidirectional"))
    )
    (net (code "83") (name "unconnected-(U5-PadRST)") (class "Default")
      (node (ref "U5") (pin "RST") (pinfunction "RST_RST") (pintype "bidirectional"))
    )
    (net (code "84") (name "unconnected-(U5-PadSWIM)") (class "Default")
      (node (ref "U5") (pin "SWIM") (pinfunction "SWIM_SWIM") (pintype "bidirectional"))
    )
  )
)
